# module.net
KiCad netlist of a schematic drawn in EAGLE
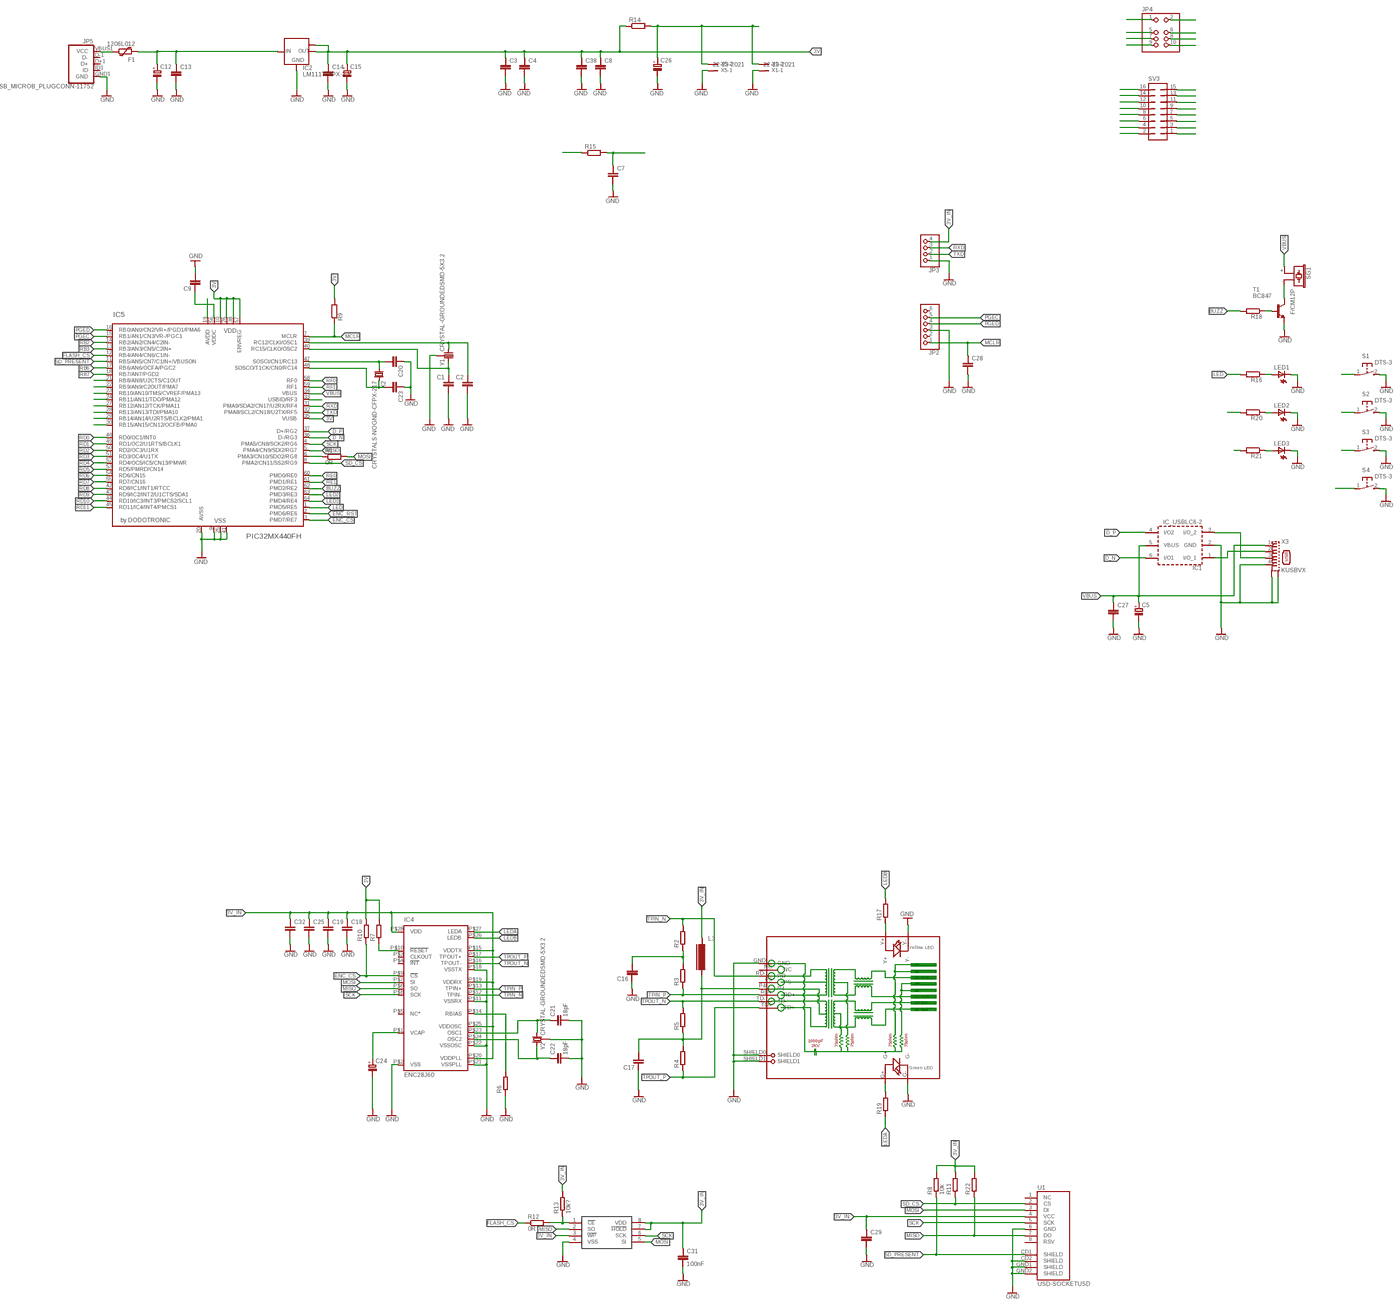
[diagram p0: schematic, sheet 1, overview]
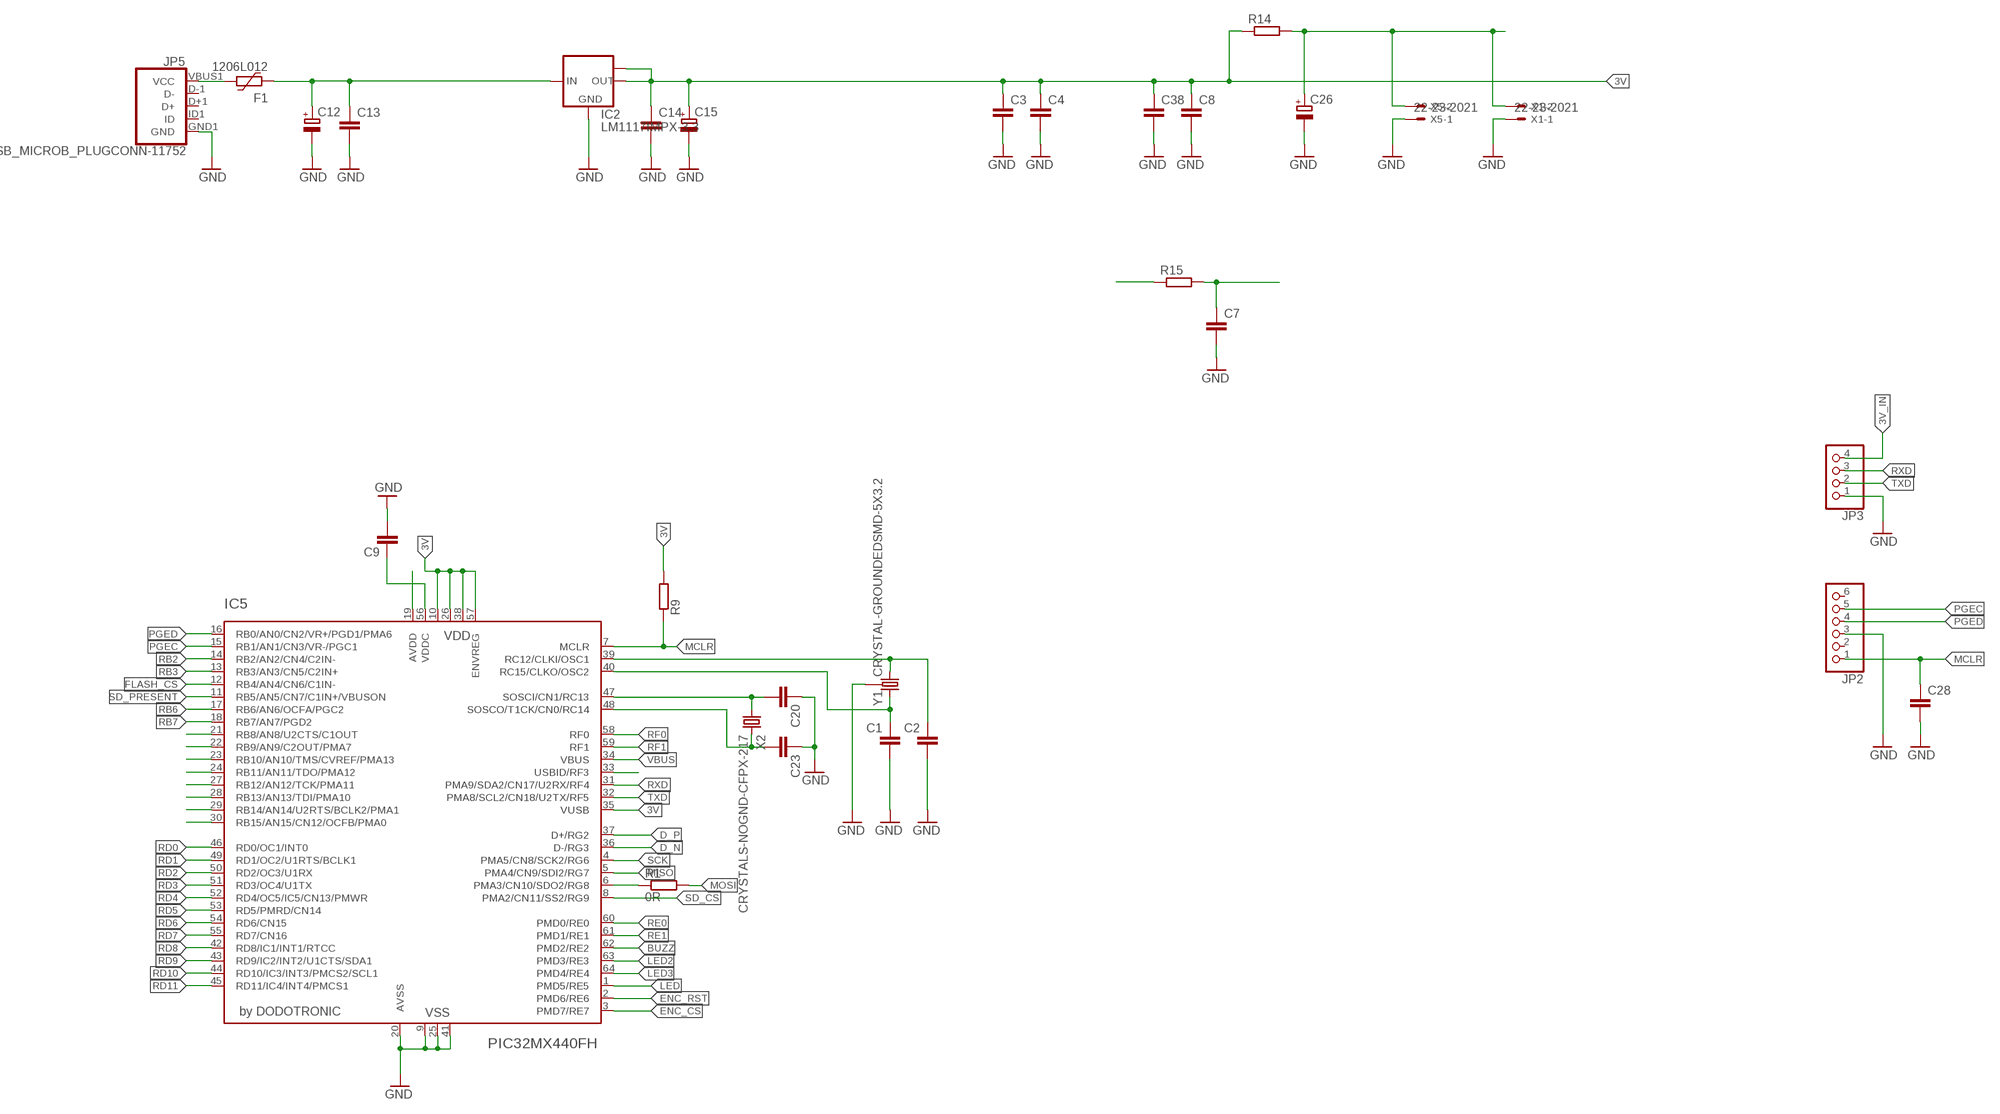
[diagram p1: schematic, sheet 1, part 1 of 4]
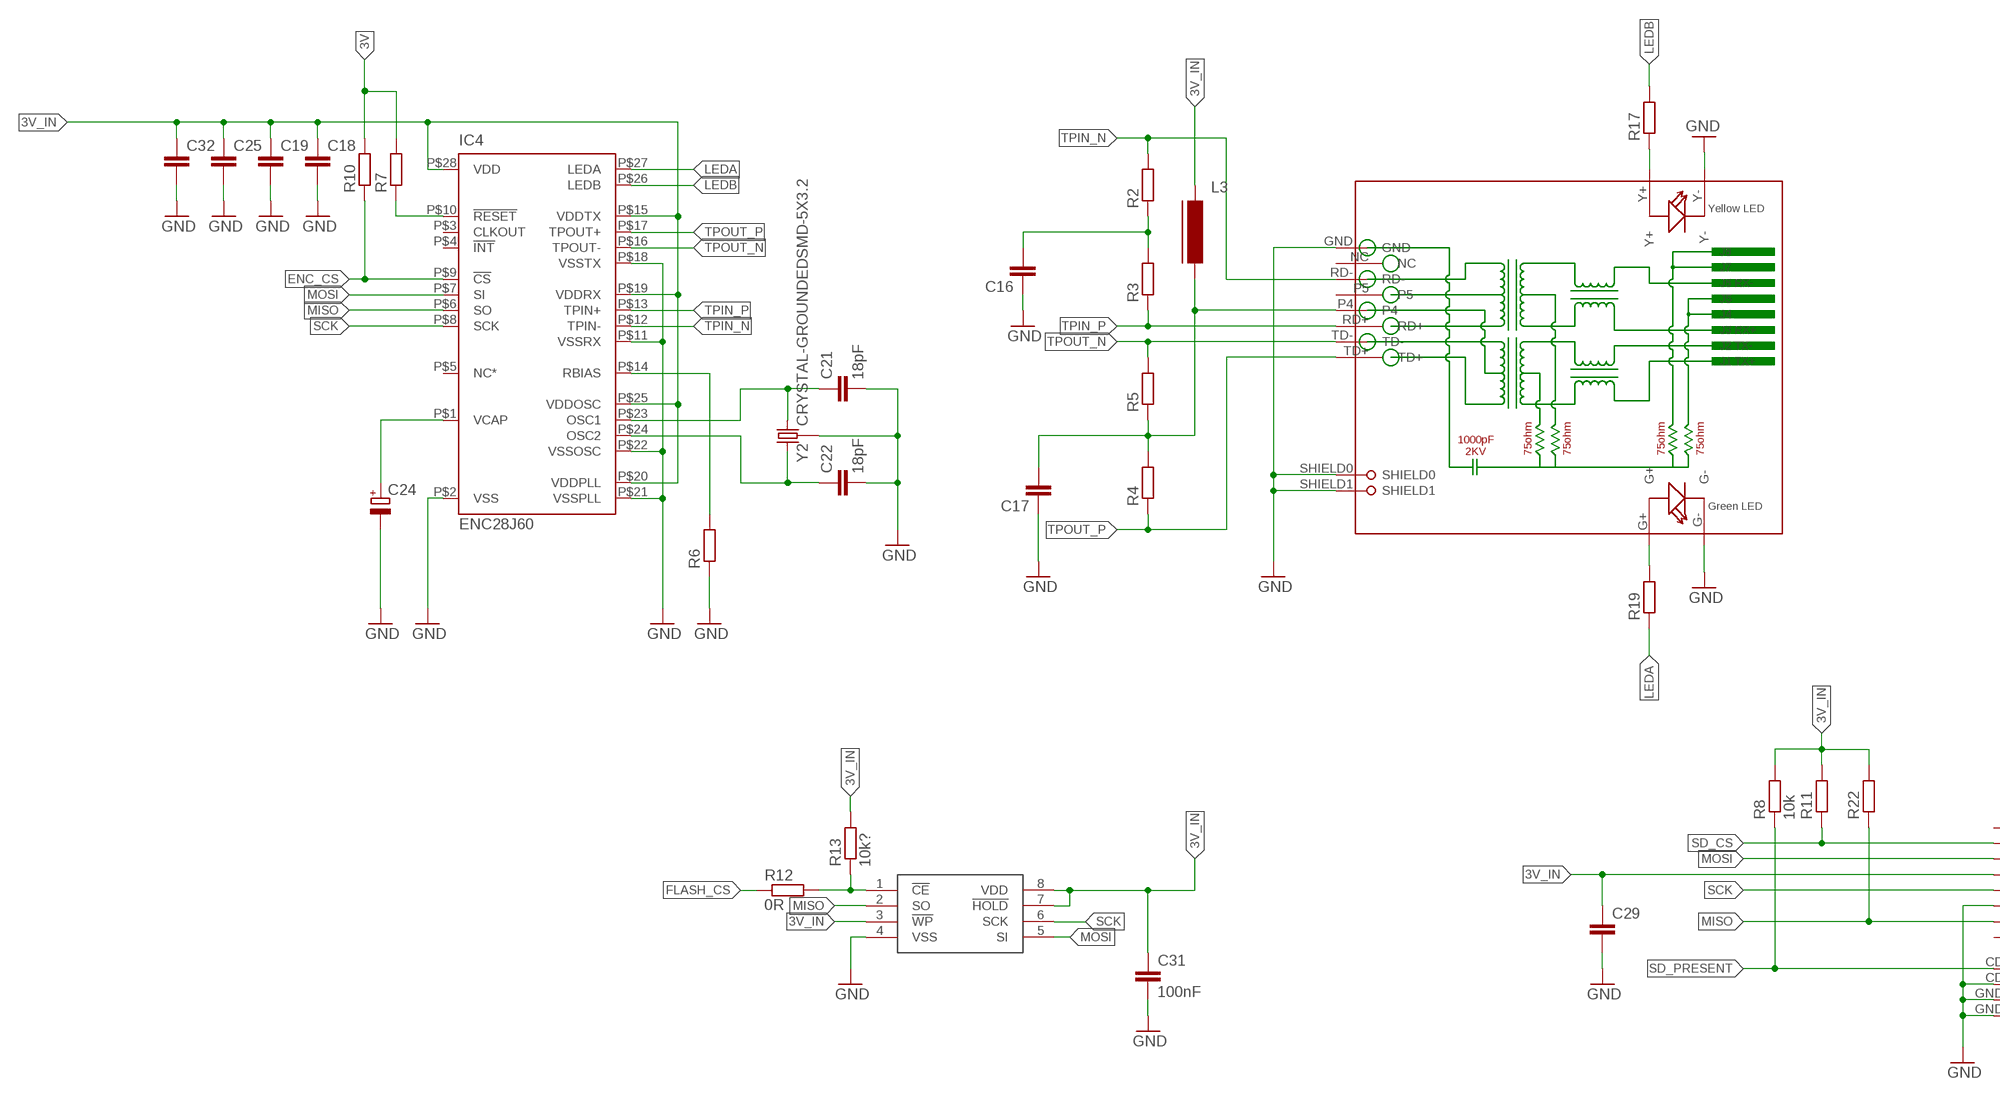
[diagram p2: schematic, sheet 1, part 2 of 4]
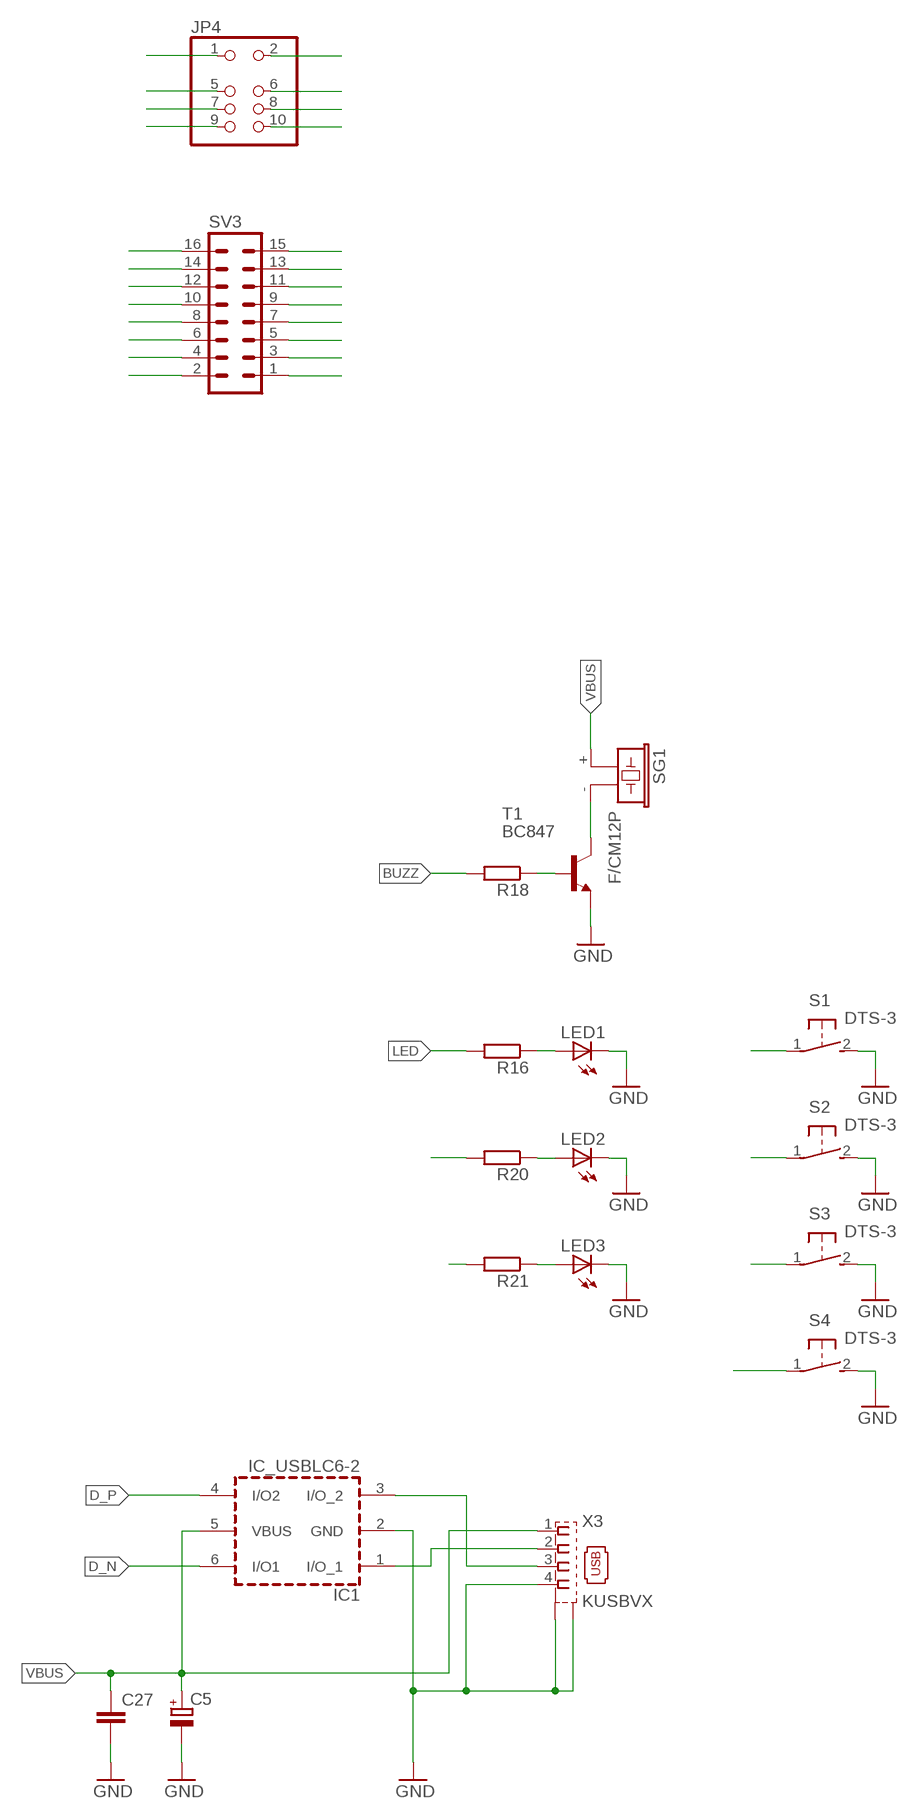
[diagram p3: schematic, sheet 1, part 3 of 4]
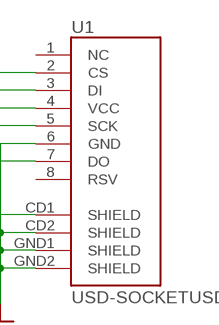
[diagram p4: schematic, sheet 1, part 4 of 4]

(export (version "E")
  (design (tool "Eeschema 10.0.6"))
  (components
    (comp (ref "C1")
      (value "C-EUC0603")
      (footprint "eagle-import:C0603")
      (libsource (lib "eagle-import") (part "C-EUC0603"))
    )
    (comp (ref "C2")
      (value "C-EUC0603")
      (footprint "eagle-import:C0603")
      (libsource (lib "eagle-import") (part "C-EUC0603"))
    )
    (comp (ref "C3")
      (value "C-EUC0402")
      (footprint "eagle-import:C0402")
      (libsource (lib "eagle-import") (part "C-EUC0402"))
    )
    (comp (ref "C4")
      (value "C-EUC0402")
      (footprint "eagle-import:C0402")
      (libsource (lib "eagle-import") (part "C-EUC0402"))
    )
    (comp (ref "C5")
      (value "CPOL-EUSMCA")
      (footprint "eagle-import:SMC_A")
      (libsource (lib "eagle-import") (part "CPOL-EUSMCA"))
    )
    (comp (ref "C7")
      (value "C-EUC0402")
      (footprint "eagle-import:C0402")
      (libsource (lib "eagle-import") (part "C-EUC0402"))
    )
    (comp (ref "C8")
      (value "C-EUC0402")
      (footprint "eagle-import:C0402")
      (libsource (lib "eagle-import") (part "C-EUC0402"))
    )
    (comp (ref "C9")
      (value "C-EUC0603")
      (footprint "eagle-import:C0603")
      (libsource (lib "eagle-import") (part "C-EUC0603"))
    )
    (comp (ref "C12")
      (value "CPOL-EUSMCB")
      (footprint "eagle-import:SMC_B")
      (libsource (lib "eagle-import") (part "CPOL-EUSMCB"))
    )
    (comp (ref "C13")
      (value "C-EUC0603")
      (footprint "eagle-import:C0603")
      (libsource (lib "eagle-import") (part "C-EUC0603"))
    )
    (comp (ref "C14")
      (value "C-EUC0603")
      (footprint "eagle-import:C0603")
      (libsource (lib "eagle-import") (part "C-EUC0603"))
    )
    (comp (ref "C15")
      (value "CPOL-EUSMCB")
      (footprint "eagle-import:SMC_B")
      (libsource (lib "eagle-import") (part "CPOL-EUSMCB"))
    )
    (comp (ref "C16")
      (value "C-EUC0603")
      (footprint "eagle-import:C0603")
      (libsource (lib "eagle-import") (part "C-EUC0603"))
    )
    (comp (ref "C17")
      (value "C-EUC0603")
      (footprint "eagle-import:C0603")
      (libsource (lib "eagle-import") (part "C-EUC0603"))
    )
    (comp (ref "C18")
      (value "C-EUC0402")
      (footprint "eagle-import:C0402")
      (libsource (lib "eagle-import") (part "C-EUC0402"))
    )
    (comp (ref "C19")
      (value "C-EUC0603")
      (footprint "eagle-import:C0603")
      (libsource (lib "eagle-import") (part "C-EUC0603"))
    )
    (comp (ref "C20")
      (value "C-EUC0603")
      (footprint "eagle-import:C0603")
      (libsource (lib "eagle-import") (part "C-EUC0603"))
    )
    (comp (ref "C21")
      (value "18pF")
      (footprint "eagle-import:C0603")
      (libsource (lib "eagle-import") (part "C-EUC0603"))
    )
    (comp (ref "C22")
      (value "18pF")
      (footprint "eagle-import:C0603")
      (libsource (lib "eagle-import") (part "C-EUC0603"))
    )
    (comp (ref "C23")
      (value "C-EUC0603")
      (footprint "eagle-import:C0603")
      (libsource (lib "eagle-import") (part "C-EUC0603"))
    )
    (comp (ref "C24")
      (value "CPOL-EUSMCA")
      (footprint "eagle-import:SMC_A")
      (libsource (lib "eagle-import") (part "CPOL-EUSMCA"))
    )
    (comp (ref "C25")
      (value "C-EUC0603")
      (footprint "eagle-import:C0603")
      (libsource (lib "eagle-import") (part "C-EUC0603"))
    )
    (comp (ref "C26")
      (value "CPOL-EUSMCA")
      (footprint "eagle-import:SMC_A")
      (libsource (lib "eagle-import") (part "CPOL-EUSMCA"))
    )
    (comp (ref "C27")
      (value "C-EUC0603")
      (footprint "eagle-import:C0603")
      (libsource (lib "eagle-import") (part "C-EUC0603"))
    )
    (comp (ref "C28")
      (value "C-EUC0603")
      (footprint "eagle-import:C0603")
      (libsource (lib "eagle-import") (part "C-EUC0603"))
    )
    (comp (ref "C29")
      (value "C-EUC0603")
      (footprint "eagle-import:C0603")
      (libsource (lib "eagle-import") (part "C-EUC0603"))
    )
    (comp (ref "C31")
      (value "100nF")
      (footprint "eagle-import:C0603")
      (libsource (lib "eagle-import") (part "C-EUC0603"))
    )
    (comp (ref "C32")
      (value "C-EUC0402")
      (footprint "eagle-import:C0402")
      (libsource (lib "eagle-import") (part "C-EUC0402"))
    )
    (comp (ref "C38")
      (value "C-EUC0603")
      (footprint "eagle-import:C0603")
      (libsource (lib "eagle-import") (part "C-EUC0603"))
    )
    (comp (ref "F1")
      (value "1206L012")
      (footprint "eagle-import:1206L")
      (fields (field (name "MF") "Littelfuse"))
      (libsource (lib "eagle-import") (part "?1206L012"))
    )
    (comp (ref "IC1")
      (value "IC_USBLC6-2")
      (footprint "eagle-import:SOT-23-6L")
      (libsource (lib "eagle-import") (part "IC_USBLC6-2"))
    )
    (comp (ref "IC2")
      (value "LM1117IMPX-3.3")
      (footprint "eagle-import:SOT223")
      (libsource (lib "eagle-import") (part "LM1117IMPX-3.3"))
    )
    (comp (ref "IC4")
      (value "ENC28J60")
      (footprint "eagle-import:TSSOP28W")
      (libsource (lib "eagle-import") (part "ENC28J60"))
    )
    (comp (ref "IC5")
      (value "PIC32MX440FH")
      (footprint "eagle-import:TQFP64-10X10")
      (libsource (lib "eagle-import") (part "PIC32MX440FH"))
    )
    (comp (ref "JP2")
      (value "PINHD-1X6")
      (footprint "eagle-import:1X06")
      (libsource (lib "eagle-import") (part "PINHD-1X6"))
    )
    (comp (ref "JP3")
      (value "PINHD-1X4")
      (footprint "eagle-import:1X04")
      (libsource (lib "eagle-import") (part "PINHD-1X4"))
    )
    (comp (ref "JP4")
      (value "PINHD-2X5")
      (footprint "eagle-import:2X05")
      (libsource (lib "eagle-import") (part "PINHD-2X5"))
    )
    (comp (ref "JP5")
      (value "USB_MICROB_PLUGCONN-11752")
      (footprint "eagle-import:USB-B-MICRO-SMD_V03")
      (libsource (lib "eagle-import") (part "USB_MICROB_PLUGCONN-11752"))
    )
    (comp (ref "L3")
      (value "FERRITE-0805")
      (footprint "eagle-import:FB805")
      (libsource (lib "eagle-import") (part "FERRITE-0805"))
    )
    (comp (ref "LED1")
      (value "LED3MM")
      (footprint "eagle-import:LED3MM")
      (libsource (lib "eagle-import") (part "LED3MM"))
    )
    (comp (ref "LED2")
      (value "LED3MM")
      (footprint "eagle-import:LED3MM")
      (libsource (lib "eagle-import") (part "LED3MM"))
    )
    (comp (ref "LED3")
      (value "LED3MM")
      (footprint "eagle-import:LED3MM")
      (libsource (lib "eagle-import") (part "LED3MM"))
    )
    (comp (ref "R1")
      (value "0R")
      (footprint "eagle-import:R0603")
      (libsource (lib "eagle-import") (part "R-EU_R0603"))
    )
    (comp (ref "R2")
      (value "R-EU_R0603")
      (footprint "eagle-import:R0603")
      (libsource (lib "eagle-import") (part "R-EU_R0603"))
    )
    (comp (ref "R3")
      (value "R-EU_R0603")
      (footprint "eagle-import:R0603")
      (libsource (lib "eagle-import") (part "R-EU_R0603"))
    )
    (comp (ref "R4")
      (value "R-EU_R0603")
      (footprint "eagle-import:R0603")
      (libsource (lib "eagle-import") (part "R-EU_R0603"))
    )
    (comp (ref "R5")
      (value "R-EU_R0603")
      (footprint "eagle-import:R0603")
      (libsource (lib "eagle-import") (part "R-EU_R0603"))
    )
    (comp (ref "R6")
      (value "R-EU_R0805")
      (footprint "eagle-import:R0805")
      (libsource (lib "eagle-import") (part "R-EU_R0805"))
    )
    (comp (ref "R7")
      (value "R-EU_R0402")
      (footprint "eagle-import:R0402")
      (libsource (lib "eagle-import") (part "R-EU_R0402"))
    )
    (comp (ref "R8")
      (value "10k")
      (footprint "eagle-import:R0603")
      (libsource (lib "eagle-import") (part "R-EU_R0603"))
    )
    (comp (ref "R9")
      (value "R-EU_R0603")
      (footprint "eagle-import:R0603")
      (libsource (lib "eagle-import") (part "R-EU_R0603"))
    )
    (comp (ref "R10")
      (value "R-EU_R0603")
      (footprint "eagle-import:R0603")
      (libsource (lib "eagle-import") (part "R-EU_R0603"))
    )
    (comp (ref "R11")
      (value "R-EU_R0603")
      (footprint "eagle-import:R0603")
      (libsource (lib "eagle-import") (part "R-EU_R0603"))
    )
    (comp (ref "R12")
      (value "0R")
      (footprint "eagle-import:R0603")
      (libsource (lib "eagle-import") (part "R-EU_R0603"))
    )
    (comp (ref "R13")
      (value "10k?")
      (footprint "eagle-import:R0603")
      (libsource (lib "eagle-import") (part "R-EU_R0603"))
    )
    (comp (ref "R14")
      (value "R-EU_R2010")
      (footprint "eagle-import:R2010")
      (libsource (lib "eagle-import") (part "R-EU_R2010"))
    )
    (comp (ref "R15")
      (value "R-EU_R0805")
      (footprint "eagle-import:R0805")
      (libsource (lib "eagle-import") (part "R-EU_R0805"))
    )
    (comp (ref "R16")
      (value "R-EU_R0603")
      (footprint "eagle-import:R0603")
      (libsource (lib "eagle-import") (part "R-EU_R0603"))
    )
    (comp (ref "R17")
      (value "R-EU_R1206")
      (footprint "eagle-import:R1206")
      (libsource (lib "eagle-import") (part "R-EU_R1206"))
    )
    (comp (ref "R18")
      (value "R-EU_R0603")
      (footprint "eagle-import:R0603")
      (libsource (lib "eagle-import") (part "R-EU_R0603"))
    )
    (comp (ref "R19")
      (value "R-EU_R1206")
      (footprint "eagle-import:R1206")
      (libsource (lib "eagle-import") (part "R-EU_R1206"))
    )
    (comp (ref "R20")
      (value "R-EU_R0603")
      (footprint "eagle-import:R0603")
      (libsource (lib "eagle-import") (part "R-EU_R0603"))
    )
    (comp (ref "R21")
      (value "R-EU_R0603")
      (footprint "eagle-import:R0603")
      (libsource (lib "eagle-import") (part "R-EU_R0603"))
    )
    (comp (ref "R22")
      (value "R-EU_R0603")
      (footprint "eagle-import:R0603")
      (libsource (lib "eagle-import") (part "R-EU_R0603"))
    )
    (comp (ref "RJ1")
      (value "HR911105A")
      (footprint "eagle-import:HR911105A")
      (libsource (lib "eagle-import") (part "HR911105A"))
    )
    (comp (ref "S1")
      (value "DTS-3")
      (footprint "eagle-import:DTS-3")
      (libsource (lib "eagle-import") (part "DTS-3"))
    )
    (comp (ref "S2")
      (value "DTS-3")
      (footprint "eagle-import:DTS-3")
      (libsource (lib "eagle-import") (part "DTS-3"))
    )
    (comp (ref "S3")
      (value "DTS-3")
      (footprint "eagle-import:DTS-3")
      (libsource (lib "eagle-import") (part "DTS-3"))
    )
    (comp (ref "S4")
      (value "DTS-3")
      (footprint "eagle-import:DTS-3")
      (libsource (lib "eagle-import") (part "DTS-3"))
    )
    (comp (ref "SG1")
      (value "F/CM12P")
      (footprint "eagle-import:F_CM12P")
      (libsource (lib "eagle-import") (part "F/CM12P"))
    )
    (comp (ref "SV3")
      (value "ML16L")
      (footprint "eagle-import:ML16L")
      (libsource (lib "eagle-import") (part "ML16L"))
    )
    (comp (ref "T1")
      (value "BC847")
      (footprint "eagle-import:SOT23")
      (libsource (lib "eagle-import") (part "BC847"))
    )
    (comp (ref "U$2")
      (value "SST25VF016BSO8M")
      (footprint "eagle-import:SO-08M")
      (libsource (lib "eagle-import") (part "SST25VF016BSO8M"))
    )
    (comp (ref "U1")
      (value "USD-SOCKETUSD")
      (footprint "eagle-import:USD-SOCKET-PP")
      (libsource (lib "eagle-import") (part "USD-SOCKETUSD"))
    )
    (comp (ref "X1")
      (value "22-23-2021")
      (footprint "eagle-import:22-23-2021")
      (fields (field (name "MF") "MOLEX"))
      (libsource (lib "eagle-import") (part "22-23-2021"))
    )
    (comp (ref "X2")
      (value "CRYSTALS-NOGND-CFPX-217")
      (footprint "eagle-import:3.2X1.5-2-PAD")
      (libsource (lib "eagle-import") (part "CRYSTALS-NOGND-CFPX-217"))
    )
    (comp (ref "X3")
      (value "KUSBVX")
      (footprint "eagle-import:KUSBVX")
      (libsource (lib "eagle-import") (part "KUSBVX"))
    )
    (comp (ref "X5")
      (value "22-23-2021")
      (footprint "eagle-import:22-23-2021")
      (fields (field (name "MF") "MOLEX"))
      (libsource (lib "eagle-import") (part "22-23-2021"))
    )
    (comp (ref "Y1")
      (value "CRYSTAL-GROUNDEDSMD-5X3.2")
      (footprint "eagle-import:CRYSTAL-SMD-5X3.2-4PAD")
      (libsource (lib "eagle-import") (part "CRYSTAL-GROUNDEDSMD-5X3.2"))
    )
    (comp (ref "Y2")
      (value "CRYSTAL-GROUNDEDSMD-5X3.2")
      (footprint "eagle-import:CRYSTAL-SMD-5X3.2-4PAD")
      (libsource (lib "eagle-import") (part "CRYSTAL-GROUNDEDSMD-5X3.2"))
    )
  )
  (nets
    (net (code "1") (name "/AV_3V") (class "Default")
      (node (ref "C7") (pin "1") (pinfunction "1_1") (pintype "passive"))
      (node (ref "IC5") (pin "19") (pinfunction "AVDD_19") (pintype "bidirectional"))
      (node (ref "R15") (pin "2") (pinfunction "2_2") (pintype "passive"))
    )
    (net (code "2") (name "/N$14") (class "Default")
      (node (ref "IC5") (pin "21") (pinfunction "RB8/AN8/U2CTS/C1OUT_21") (pintype "bidirectional"))
      (node (ref "JP4") (pin "9") (pinfunction "9_9") (pintype "passive"))
    )
    (net (code "3") (name "/N$15") (class "Default")
      (node (ref "IC5") (pin "22") (pinfunction "RB9/AN9/C2OUT/PMA7_22") (pintype "bidirectional"))
      (node (ref "JP4") (pin "10") (pinfunction "10_10") (pintype "passive"))
    )
    (net (code "4") (name "/N$16") (class "Default")
      (node (ref "IC5") (pin "23") (pinfunction "RB10/AN10/TMS/CVREF/PMA13_23") (pintype "bidirectional"))
      (node (ref "JP4") (pin "7") (pinfunction "7_7") (pintype "passive"))
    )
    (net (code "5") (name "/N$18") (class "Default")
      (node (ref "IC5") (pin "24") (pinfunction "RB11/AN11/TDO/PMA12_24") (pintype "bidirectional"))
      (node (ref "JP4") (pin "8") (pinfunction "8_8") (pintype "passive"))
    )
    (net (code "6") (name "/N$20") (class "Default")
      (node (ref "IC5") (pin "28") (pinfunction "RB13/AN13/TDI/PMA10_28") (pintype "bidirectional"))
      (node (ref "JP4") (pin "5") (pinfunction "5_5") (pintype "passive"))
    )
    (net (code "7") (name "/N$21") (class "Default")
      (node (ref "IC5") (pin "29") (pinfunction "RB14/AN14/U2RTS/BCLK2/PMA1_29") (pintype "bidirectional"))
      (node (ref "JP4") (pin "6") (pinfunction "6_6") (pintype "passive"))
    )
    (net (code "8") (name "/N$24") (class "Default")
      (node (ref "IC5") (pin "30") (pinfunction "RB15/AN15/CN12/OCFB/PMA0_30") (pintype "bidirectional"))
      (node (ref "JP4") (pin "1") (pinfunction "1_1") (pintype "passive"))
    )
    (net (code "9") (name "/N$25") (class "Default")
      (node (ref "IC5") (pin "33") (pinfunction "USBID/RF3_33") (pintype "bidirectional"))
      (node (ref "JP4") (pin "2") (pinfunction "2_2") (pintype "passive"))
    )
    (net (code "10") (name "3V") (class "Default")
      (node (ref "C14") (pin "1") (pinfunction "1_1") (pintype "passive"))
      (node (ref "C15") (pin "+") (pinfunction "+_+") (pintype "passive"))
      (node (ref "C3") (pin "1") (pinfunction "1_1") (pintype "passive"))
      (node (ref "C38") (pin "1") (pinfunction "1_1") (pintype "passive"))
      (node (ref "C4") (pin "1") (pinfunction "1_1") (pintype "passive"))
      (node (ref "C8") (pin "1") (pinfunction "1_1") (pintype "passive"))
      (node (ref "IC2") (pin "2") (pinfunction "OUT_2") (pintype "passive"))
      (node (ref "IC2") (pin "TAB") (pinfunction "OUT1_TAB") (pintype "passive"))
      (node (ref "IC5") (pin "10") (pinfunction "VDD_10") (pintype "power_in"))
      (node (ref "IC5") (pin "26") (pinfunction "VDD_26") (pintype "power_in"))
      (node (ref "IC5") (pin "35") (pinfunction "VUSB_35") (pintype "bidirectional"))
      (node (ref "IC5") (pin "38") (pinfunction "VDD_38") (pintype "power_in"))
      (node (ref "IC5") (pin "57") (pinfunction "ENVREG_57") (pintype "bidirectional"))
      (node (ref "R10") (pin "2") (pinfunction "2_2") (pintype "passive"))
      (node (ref "R14") (pin "1") (pinfunction "1_1") (pintype "passive"))
      (node (ref "R7") (pin "2") (pinfunction "2_2") (pintype "passive"))
      (node (ref "R9") (pin "2") (pinfunction "2_2") (pintype "passive"))
    )
    (net (code "11") (name "3V_IN") (class "Default")
      (node (ref "C18") (pin "1") (pinfunction "1_1") (pintype "passive"))
      (node (ref "C19") (pin "1") (pinfunction "1_1") (pintype "passive"))
      (node (ref "C25") (pin "1") (pinfunction "1_1") (pintype "passive"))
      (node (ref "C26") (pin "+") (pinfunction "+_+") (pintype "passive"))
      (node (ref "C29") (pin "1") (pinfunction "1_1") (pintype "passive"))
      (node (ref "C31") (pin "1") (pinfunction "1_1") (pintype "passive"))
      (node (ref "C32") (pin "1") (pinfunction "1_1") (pintype "passive"))
      (node (ref "IC4") (pin "P$15") (pinfunction "VDDTX_P$15") (pintype "input"))
      (node (ref "IC4") (pin "P$19") (pinfunction "VDDRX_P$19") (pintype "input"))
      (node (ref "IC4") (pin "P$20") (pinfunction "VDDPLL_P$20") (pintype "input"))
      (node (ref "IC4") (pin "P$25") (pinfunction "VDDOSC_P$25") (pintype "input"))
      (node (ref "IC4") (pin "P$28") (pinfunction "VDD_P$28") (pintype "input"))
      (node (ref "JP3") (pin "4") (pinfunction "4_4") (pintype "passive"))
      (node (ref "L3") (pin "1") (pinfunction "1_1") (pintype "passive"))
      (node (ref "R11") (pin "2") (pinfunction "2_2") (pintype "passive"))
      (node (ref "R13") (pin "2") (pinfunction "2_2") (pintype "passive"))
      (node (ref "R14") (pin "2") (pinfunction "2_2") (pintype "passive"))
      (node (ref "R15") (pin "1") (pinfunction "1_1") (pintype "passive"))
      (node (ref "R22") (pin "2") (pinfunction "2_2") (pintype "passive"))
      (node (ref "R8") (pin "2") (pinfunction "2_2") (pintype "passive"))
      (node (ref "U$2") (pin "3") (pinfunction "~{WP}_3") (pintype "bidirectional"))
      (node (ref "U$2") (pin "7") (pinfunction "~{HOLD}_7") (pintype "bidirectional"))
      (node (ref "U$2") (pin "8") (pinfunction "VDD_8") (pintype "bidirectional"))
      (node (ref "U1") (pin "4") (pinfunction "VCC_4") (pintype "bidirectional"))
      (node (ref "X1") (pin "2") (pinfunction "S_2") (pintype "passive"))
      (node (ref "X5") (pin "2") (pinfunction "S_2") (pintype "passive"))
    )
    (net (code "12") (name "BUZZ") (class "Default")
      (node (ref "IC5") (pin "62") (pinfunction "PMD2/RE2_62") (pintype "bidirectional"))
      (node (ref "R18") (pin "2") (pinfunction "2_2") (pintype "passive"))
    )
    (net (code "13") (name "D_N") (class "Default")
      (node (ref "IC1") (pin "6") (pinfunction "I/O1_6") (pintype "bidirectional"))
      (node (ref "IC5") (pin "36") (pinfunction "D-/RG3_36") (pintype "bidirectional"))
    )
    (net (code "14") (name "D_P") (class "Default")
      (node (ref "IC1") (pin "4") (pinfunction "I/O2_4") (pintype "bidirectional"))
      (node (ref "IC5") (pin "37") (pinfunction "D+/RG2_37") (pintype "bidirectional"))
    )
    (net (code "15") (name "ENC_CS") (class "Default")
      (node (ref "IC4") (pin "P$9") (pinfunction "~{CS}_P$9") (pintype "input"))
      (node (ref "IC5") (pin "3") (pinfunction "PMD7/RE7_3") (pintype "bidirectional"))
      (node (ref "R10") (pin "1") (pinfunction "1_1") (pintype "passive"))
    )
    (net (code "16") (name "ENC_RST") (class "Default")
      (node (ref "IC4") (pin "P$10") (pinfunction "~{RESET}_P$10") (pintype "input"))
      (node (ref "IC5") (pin "2") (pinfunction "PMD6/RE6_2") (pintype "bidirectional"))
      (node (ref "R7") (pin "1") (pinfunction "1_1") (pintype "passive"))
    )
    (net (code "17") (name "FLASH_CS") (class "Default")
      (node (ref "IC5") (pin "12") (pinfunction "RB4/AN4/CN6/C1IN-_12") (pintype "bidirectional"))
      (node (ref "R12") (pin "1") (pinfunction "1_1") (pintype "passive"))
    )
    (net (code "18") (name "GND") (class "Default")
      (node (ref "C1") (pin "2") (pinfunction "2_2") (pintype "passive"))
      (node (ref "C12") (pin "-") (pinfunction "-_-") (pintype "passive"))
      (node (ref "C13") (pin "2") (pinfunction "2_2") (pintype "passive"))
      (node (ref "C14") (pin "2") (pinfunction "2_2") (pintype "passive"))
      (node (ref "C15") (pin "-") (pinfunction "-_-") (pintype "passive"))
      (node (ref "C16") (pin "1") (pinfunction "1_1") (pintype "passive"))
      (node (ref "C17") (pin "1") (pinfunction "1_1") (pintype "passive"))
      (node (ref "C18") (pin "2") (pinfunction "2_2") (pintype "passive"))
      (node (ref "C19") (pin "2") (pinfunction "2_2") (pintype "passive"))
      (node (ref "C2") (pin "2") (pinfunction "2_2") (pintype "passive"))
      (node (ref "C20") (pin "1") (pinfunction "1_1") (pintype "passive"))
      (node (ref "C21") (pin "2") (pinfunction "2_2") (pintype "passive"))
      (node (ref "C22") (pin "2") (pinfunction "2_2") (pintype "passive"))
      (node (ref "C23") (pin "1") (pinfunction "1_1") (pintype "passive"))
      (node (ref "C24") (pin "-") (pinfunction "-_-") (pintype "passive"))
      (node (ref "C25") (pin "2") (pinfunction "2_2") (pintype "passive"))
      (node (ref "C26") (pin "-") (pinfunction "-_-") (pintype "passive"))
      (node (ref "C27") (pin "2") (pinfunction "2_2") (pintype "passive"))
      (node (ref "C28") (pin "2") (pinfunction "2_2") (pintype "passive"))
      (node (ref "C29") (pin "2") (pinfunction "2_2") (pintype "passive"))
      (node (ref "C3") (pin "2") (pinfunction "2_2") (pintype "passive"))
      (node (ref "C31") (pin "2") (pinfunction "2_2") (pintype "passive"))
      (node (ref "C32") (pin "2") (pinfunction "2_2") (pintype "passive"))
      (node (ref "C38") (pin "2") (pinfunction "2_2") (pintype "passive"))
      (node (ref "C4") (pin "2") (pinfunction "2_2") (pintype "passive"))
      (node (ref "C5") (pin "-") (pinfunction "-_-") (pintype "passive"))
      (node (ref "C7") (pin "2") (pinfunction "2_2") (pintype "passive"))
      (node (ref "C8") (pin "2") (pinfunction "2_2") (pintype "passive"))
      (node (ref "C9") (pin "2") (pinfunction "2_2") (pintype "passive"))
      (node (ref "IC1") (pin "2") (pinfunction "GND_2") (pintype "bidirectional"))
      (node (ref "IC2") (pin "1") (pinfunction "GND_1") (pintype "input"))
      (node (ref "IC4") (pin "P$11") (pinfunction "VSSRX_P$11") (pintype "input"))
      (node (ref "IC4") (pin "P$18") (pinfunction "VSSTX_P$18") (pintype "input"))
      (node (ref "IC4") (pin "P$2") (pinfunction "VSS_P$2") (pintype "input"))
      (node (ref "IC4") (pin "P$21") (pinfunction "VSSPLL_P$21") (pintype "input"))
      (node (ref "IC4") (pin "P$22") (pinfunction "VSSOSC_P$22") (pintype "input"))
      (node (ref "IC5") (pin "20") (pinfunction "AVSS_20") (pintype "bidirectional"))
      (node (ref "IC5") (pin "25") (pinfunction "VSS_25") (pintype "power_in"))
      (node (ref "IC5") (pin "41") (pinfunction "VSS_41") (pintype "power_in"))
      (node (ref "IC5") (pin "9") (pinfunction "VSS_9") (pintype "power_in"))
      (node (ref "JP2") (pin "3") (pinfunction "3_3") (pintype "passive"))
      (node (ref "JP3") (pin "1") (pinfunction "1_1") (pintype "passive"))
      (node (ref "JP5") (pin "GND1") (pinfunction "GND_GND1") (pintype "bidirectional"))
      (node (ref "LED1") (pin "K") (pinfunction "C_K") (pintype "passive"))
      (node (ref "LED2") (pin "K") (pinfunction "C_K") (pintype "passive"))
      (node (ref "LED3") (pin "K") (pinfunction "C_K") (pintype "passive"))
      (node (ref "R6") (pin "1") (pinfunction "1_1") (pintype "passive"))
      (node (ref "RJ1") (pin "G-") (pinfunction "G-_G-") (pintype "bidirectional"))
      (node (ref "RJ1") (pin "GND") (pinfunction "GND_GND") (pintype "bidirectional"))
      (node (ref "RJ1") (pin "SHIELD0") (pinfunction "SHIELD0_SHIELD0") (pintype "bidirectional"))
      (node (ref "RJ1") (pin "SHIELD1") (pinfunction "SHIELD1_SHIELD1") (pintype "bidirectional"))
      (node (ref "RJ1") (pin "Y-") (pinfunction "Y-_Y-") (pintype "bidirectional"))
      (node (ref "S1") (pin "2") (pinfunction "2_2") (pintype "passive"))
      (node (ref "S2") (pin "2") (pinfunction "2_2") (pintype "passive"))
      (node (ref "S3") (pin "2") (pinfunction "2_2") (pintype "passive"))
      (node (ref "S4") (pin "2") (pinfunction "2_2") (pintype "passive"))
      (node (ref "T1") (pin "2") (pinfunction "E_2") (pintype "passive"))
      (node (ref "U$2") (pin "4") (pinfunction "VSS_4") (pintype "bidirectional"))
      (node (ref "U1") (pin "6") (pinfunction "GND_6") (pintype "bidirectional"))
      (node (ref "U1") (pin "CD2") (pinfunction "SHIELD_CD2") (pintype "bidirectional"))
      (node (ref "U1") (pin "GND1") (pinfunction "SHIELD_GND1") (pintype "bidirectional"))
      (node (ref "U1") (pin "GND2") (pinfunction "SHIELD_GND2") (pintype "bidirectional"))
      (node (ref "X1") (pin "1") (pinfunction "S_1") (pintype "passive"))
      (node (ref "X3") (pin "4") (pinfunction "4_4") (pintype "passive"))
      (node (ref "X3") (pin "M1") (pinfunction "S1_M1") (pintype "passive"))
      (node (ref "X3") (pin "M2") (pinfunction "S2_M2") (pintype "passive"))
      (node (ref "X5") (pin "1") (pinfunction "S_1") (pintype "passive"))
      (node (ref "Y1") (pin "2") (pinfunction "3_2") (pintype "passive"))
      (node (ref "Y1") (pin "4") (pinfunction "3_4") (pintype "passive"))
      (node (ref "Y2") (pin "2") (pinfunction "3_2") (pintype "passive"))
      (node (ref "Y2") (pin "4") (pinfunction "3_4") (pintype "passive"))
    )
    (net (code "19") (name "LED") (class "Default")
      (node (ref "IC5") (pin "1") (pinfunction "PMD5/RE5_1") (pintype "bidirectional"))
      (node (ref "R16") (pin "2") (pinfunction "2_2") (pintype "passive"))
    )
    (net (code "20") (name "LED2") (class "Default")
      (node (ref "IC5") (pin "63") (pinfunction "PMD3/RE3_63") (pintype "bidirectional"))
      (node (ref "R20") (pin "2") (pinfunction "2_2") (pintype "passive"))
    )
    (net (code "21") (name "LED3") (class "Default")
      (node (ref "IC5") (pin "64") (pinfunction "PMD4/RE4_64") (pintype "bidirectional"))
      (node (ref "R21") (pin "2") (pinfunction "2_2") (pintype "passive"))
    )
    (net (code "22") (name "LEDA") (class "Default")
      (node (ref "IC4") (pin "P$27") (pinfunction "LEDA_P$27") (pintype "output"))
      (node (ref "R19") (pin "1") (pinfunction "1_1") (pintype "passive"))
    )
    (net (code "23") (name "LEDB") (class "Default")
      (node (ref "IC4") (pin "P$26") (pinfunction "LEDB_P$26") (pintype "output"))
      (node (ref "R17") (pin "2") (pinfunction "2_2") (pintype "passive"))
    )
    (net (code "24") (name "MCLR") (class "Default")
      (node (ref "C28") (pin "1") (pinfunction "1_1") (pintype "passive"))
      (node (ref "IC5") (pin "7") (pinfunction "MCLR_7") (pintype "bidirectional"))
      (node (ref "JP2") (pin "1") (pinfunction "1_1") (pintype "passive"))
      (node (ref "R9") (pin "1") (pinfunction "1_1") (pintype "passive"))
    )
    (net (code "25") (name "MISO") (class "Default")
      (node (ref "IC4") (pin "P$6") (pinfunction "SO_P$6") (pintype "output"))
      (node (ref "IC5") (pin "5") (pinfunction "PMA4/CN9/SDI2/RG7_5") (pintype "bidirectional"))
      (node (ref "R22") (pin "1") (pinfunction "1_1") (pintype "passive"))
      (node (ref "U$2") (pin "2") (pinfunction "SO_2") (pintype "bidirectional"))
      (node (ref "U1") (pin "7") (pinfunction "DO_7") (pintype "bidirectional"))
    )
    (net (code "26") (name "MOSI") (class "Default")
      (node (ref "IC4") (pin "P$7") (pinfunction "SI_P$7") (pintype "input"))
      (node (ref "R1") (pin "2") (pinfunction "2_2") (pintype "passive"))
      (node (ref "U$2") (pin "5") (pinfunction "SI_5") (pintype "bidirectional"))
      (node (ref "U1") (pin "3") (pinfunction "DI_3") (pintype "bidirectional"))
    )
    (net (code "27") (name "Net-(C16-Pad2)") (class "Default")
      (node (ref "C16") (pin "2") (pinfunction "2_2") (pintype "passive"))
      (node (ref "R2") (pin "1") (pinfunction "1_1") (pintype "passive"))
      (node (ref "R3") (pin "2") (pinfunction "2_2") (pintype "passive"))
    )
    (net (code "28") (name "Net-(C17-Pad2)") (class "Default")
      (node (ref "C17") (pin "2") (pinfunction "2_2") (pintype "passive"))
      (node (ref "L3") (pin "2") (pinfunction "2_2") (pintype "passive"))
      (node (ref "R4") (pin "2") (pinfunction "2_2") (pintype "passive"))
      (node (ref "R5") (pin "1") (pinfunction "1_1") (pintype "passive"))
      (node (ref "RJ1") (pin "P4") (pinfunction "P4_P4") (pintype "bidirectional"))
    )
    (net (code "29") (name "Net-(IC1-I{slash}O_1)") (class "Default")
      (node (ref "IC1") (pin "1") (pinfunction "I/O_1_1") (pintype "bidirectional"))
      (node (ref "X3") (pin "2") (pinfunction "2_2") (pintype "passive"))
    )
    (net (code "30") (name "Net-(IC1-I{slash}O_2)") (class "Default")
      (node (ref "IC1") (pin "3") (pinfunction "I/O_2_3") (pintype "bidirectional"))
      (node (ref "X3") (pin "3") (pinfunction "3_3") (pintype "passive"))
    )
    (net (code "31") (name "Net-(IC4-OSC1)") (class "Default")
      (node (ref "C21") (pin "1") (pinfunction "1_1") (pintype "passive"))
      (node (ref "IC4") (pin "P$23") (pinfunction "OSC1_P$23") (pintype "input"))
      (node (ref "Y2") (pin "1") (pinfunction "2_1") (pintype "passive"))
    )
    (net (code "32") (name "Net-(IC4-OSC2)") (class "Default")
      (node (ref "C22") (pin "1") (pinfunction "1_1") (pintype "passive"))
      (node (ref "IC4") (pin "P$24") (pinfunction "OSC2_P$24") (pintype "output"))
      (node (ref "Y2") (pin "3") (pinfunction "1_3") (pintype "passive"))
    )
    (net (code "33") (name "Net-(IC4-RBIAS)") (class "Default")
      (node (ref "IC4") (pin "P$14") (pinfunction "RBIAS_P$14") (pintype "input"))
      (node (ref "R6") (pin "2") (pinfunction "2_2") (pintype "passive"))
    )
    (net (code "34") (name "Net-(IC4-VCAP)") (class "Default")
      (node (ref "C24") (pin "+") (pinfunction "+_+") (pintype "passive"))
      (node (ref "IC4") (pin "P$1") (pinfunction "VCAP_P$1") (pintype "input"))
    )
    (net (code "35") (name "Net-(IC5-PMA3{slash}CN10{slash}SDO2{slash}RG8)") (class "Default")
      (node (ref "IC5") (pin "6") (pinfunction "PMA3/CN10/SDO2/RG8_6") (pintype "bidirectional"))
      (node (ref "R1") (pin "1") (pinfunction "1_1") (pintype "passive"))
    )
    (net (code "36") (name "Net-(IC5-RC12{slash}CLKI{slash}OSC1)") (class "Default")
      (node (ref "C2") (pin "1") (pinfunction "1_1") (pintype "passive"))
      (node (ref "IC5") (pin "39") (pinfunction "RC12/CLKI/OSC1_39") (pintype "bidirectional"))
      (node (ref "Y1") (pin "1") (pinfunction "2_1") (pintype "passive"))
    )
    (net (code "37") (name "Net-(IC5-RC15{slash}CLKO{slash}OSC2)") (class "Default")
      (node (ref "C1") (pin "1") (pinfunction "1_1") (pintype "passive"))
      (node (ref "IC5") (pin "40") (pinfunction "RC15/CLKO/OSC2_40") (pintype "bidirectional"))
      (node (ref "Y1") (pin "3") (pinfunction "1_3") (pintype "passive"))
    )
    (net (code "38") (name "Net-(IC5-SOSCI{slash}CN1{slash}RC13)") (class "Default")
      (node (ref "C20") (pin "2") (pinfunction "2_2") (pintype "passive"))
      (node (ref "IC5") (pin "47") (pinfunction "SOSCI/CN1/RC13_47") (pintype "bidirectional"))
      (node (ref "X2") (pin "1") (pinfunction "1_1") (pintype "passive"))
    )
    (net (code "39") (name "Net-(IC5-SOSCO{slash}T1CK{slash}CN0{slash}RC14)") (class "Default")
      (node (ref "C23") (pin "2") (pinfunction "2_2") (pintype "passive"))
      (node (ref "IC5") (pin "48") (pinfunction "SOSCO/T1CK/CN0/RC14_48") (pintype "bidirectional"))
      (node (ref "X2") (pin "2") (pinfunction "2_2") (pintype "passive"))
    )
    (net (code "40") (name "Net-(IC5-VDDC)") (class "Default")
      (node (ref "C9") (pin "1") (pinfunction "1_1") (pintype "passive"))
      (node (ref "IC5") (pin "56") (pinfunction "VDDC_56") (pintype "bidirectional"))
    )
    (net (code "41") (name "Net-(JP5-VCC)") (class "Default")
      (node (ref "F1") (pin "1") (pinfunction "1_1") (pintype "passive"))
      (node (ref "JP5") (pin "VBUS1") (pinfunction "VCC_VBUS1") (pintype "bidirectional"))
    )
    (net (code "42") (name "Net-(LED1-PadA)") (class "Default")
      (node (ref "LED1") (pin "A") (pinfunction "A_A") (pintype "passive"))
      (node (ref "R16") (pin "1") (pinfunction "1_1") (pintype "passive"))
    )
    (net (code "43") (name "Net-(LED2-PadA)") (class "Default")
      (node (ref "LED2") (pin "A") (pinfunction "A_A") (pintype "passive"))
      (node (ref "R20") (pin "1") (pinfunction "1_1") (pintype "passive"))
    )
    (net (code "44") (name "Net-(LED3-PadA)") (class "Default")
      (node (ref "LED3") (pin "A") (pinfunction "A_A") (pintype "passive"))
      (node (ref "R21") (pin "1") (pinfunction "1_1") (pintype "passive"))
    )
    (net (code "45") (name "Net-(R17-Pad1)") (class "Default")
      (node (ref "R17") (pin "1") (pinfunction "1_1") (pintype "passive"))
      (node (ref "RJ1") (pin "Y+") (pinfunction "Y+_Y+") (pintype "bidirectional"))
    )
    (net (code "46") (name "Net-(R19-Pad2)") (class "Default")
      (node (ref "R19") (pin "2") (pinfunction "2_2") (pintype "passive"))
      (node (ref "RJ1") (pin "G+") (pinfunction "G+_G+") (pintype "bidirectional"))
    )
    (net (code "47") (name "Net-(SG1-2)") (class "Default")
      (node (ref "SG1") (pin "-") (pinfunction "2_-") (pintype "passive"))
      (node (ref "T1") (pin "3") (pinfunction "C_3") (pintype "passive"))
    )
    (net (code "48") (name "Net-(T1-B)") (class "Default")
      (node (ref "R18") (pin "1") (pinfunction "1_1") (pintype "passive"))
      (node (ref "T1") (pin "1") (pinfunction "B_1") (pintype "passive"))
    )
    (net (code "49") (name "Net-(U$2-~{CE})") (class "Default")
      (node (ref "R12") (pin "2") (pinfunction "2_2") (pintype "passive"))
      (node (ref "R13") (pin "1") (pinfunction "1_1") (pintype "passive"))
      (node (ref "U$2") (pin "1") (pinfunction "~{CE}_1") (pintype "bidirectional"))
    )
    (net (code "50") (name "PGEC") (class "Default")
      (node (ref "IC5") (pin "15") (pinfunction "RB1/AN1/CN3/VR-/PGC1_15") (pintype "bidirectional"))
      (node (ref "JP2") (pin "5") (pinfunction "5_5") (pintype "passive"))
    )
    (net (code "51") (name "PGED") (class "Default")
      (node (ref "IC5") (pin "16") (pinfunction "RB0/AN0/CN2/VR+/PGD1/PMA6_16") (pintype "bidirectional"))
      (node (ref "JP2") (pin "4") (pinfunction "4_4") (pintype "passive"))
    )
    (net (code "52") (name "RB2") (class "Default")
      (node (ref "IC5") (pin "14") (pinfunction "RB2/AN2/CN4/C2IN-_14") (pintype "bidirectional"))
      (node (ref "S2") (pin "1") (pinfunction "1_1") (pintype "passive"))
    )
    (net (code "53") (name "RB3") (class "Default")
      (node (ref "IC5") (pin "13") (pinfunction "RB3/AN3/CN5/C2IN+_13") (pintype "bidirectional"))
      (node (ref "S1") (pin "1") (pinfunction "1_1") (pintype "passive"))
    )
    (net (code "54") (name "RB6") (class "Default")
      (node (ref "IC5") (pin "17") (pinfunction "RB6/AN6/OCFA/PGC2_17") (pintype "bidirectional"))
      (node (ref "S3") (pin "1") (pinfunction "1_1") (pintype "passive"))
    )
    (net (code "55") (name "RB7") (class "Default")
      (node (ref "IC5") (pin "18") (pinfunction "RB7/AN7/PGD2_18") (pintype "bidirectional"))
      (node (ref "S4") (pin "1") (pinfunction "1_1") (pintype "passive"))
    )
    (net (code "56") (name "RD0") (class "Default")
      (node (ref "IC5") (pin "46") (pinfunction "RD0/OC1/INT0_46") (pintype "bidirectional"))
      (node (ref "SV3") (pin "6") (pinfunction "6_6") (pintype "passive"))
    )
    (net (code "57") (name "RD1") (class "Default")
      (node (ref "IC5") (pin "49") (pinfunction "RD1/OC2/U1RTS/BCLK1_49") (pintype "bidirectional"))
      (node (ref "SV3") (pin "5") (pinfunction "5_5") (pintype "passive"))
    )
    (net (code "58") (name "RD2") (class "Default")
      (node (ref "IC5") (pin "50") (pinfunction "RD2/OC3/U1RX_50") (pintype "bidirectional"))
      (node (ref "SV3") (pin "8") (pinfunction "8_8") (pintype "passive"))
    )
    (net (code "59") (name "RD3") (class "Default")
      (node (ref "IC5") (pin "51") (pinfunction "RD3/OC4/U1TX_51") (pintype "bidirectional"))
      (node (ref "SV3") (pin "7") (pinfunction "7_7") (pintype "passive"))
    )
    (net (code "60") (name "RD4") (class "Default")
      (node (ref "IC5") (pin "52") (pinfunction "RD4/OC5/IC5/CN13/PMWR_52") (pintype "bidirectional"))
      (node (ref "SV3") (pin "10") (pinfunction "10_10") (pintype "passive"))
    )
    (net (code "61") (name "RD5") (class "Default")
      (node (ref "IC5") (pin "53") (pinfunction "RD5/PMRD/CN14_53") (pintype "bidirectional"))
      (node (ref "SV3") (pin "9") (pinfunction "9_9") (pintype "passive"))
    )
    (net (code "62") (name "RD6") (class "Default")
      (node (ref "IC5") (pin "54") (pinfunction "RD6/CN15_54") (pintype "bidirectional"))
      (node (ref "SV3") (pin "12") (pinfunction "12_12") (pintype "passive"))
    )
    (net (code "63") (name "RD7") (class "Default")
      (node (ref "IC5") (pin "55") (pinfunction "RD7/CN16_55") (pintype "bidirectional"))
      (node (ref "SV3") (pin "11") (pinfunction "11_11") (pintype "passive"))
    )
    (net (code "64") (name "RD8") (class "Default")
      (node (ref "IC5") (pin "42") (pinfunction "RD8/IC1/INT1/RTCC_42") (pintype "bidirectional"))
      (node (ref "SV3") (pin "2") (pinfunction "2_2") (pintype "passive"))
    )
    (net (code "65") (name "RD9") (class "Default")
      (node (ref "IC5") (pin "43") (pinfunction "RD9/IC2/INT2/U1CTS/SDA1_43") (pintype "bidirectional"))
      (node (ref "SV3") (pin "1") (pinfunction "1_1") (pintype "passive"))
    )
    (net (code "66") (name "RD10") (class "Default")
      (node (ref "IC5") (pin "44") (pinfunction "RD10/IC3/INT3/PMCS2/SCL1_44") (pintype "bidirectional"))
      (node (ref "SV3") (pin "4") (pinfunction "4_4") (pintype "passive"))
    )
    (net (code "67") (name "RD11") (class "Default")
      (node (ref "IC5") (pin "45") (pinfunction "RD11/IC4/INT4/PMCS1_45") (pintype "bidirectional"))
      (node (ref "SV3") (pin "3") (pinfunction "3_3") (pintype "passive"))
    )
    (net (code "68") (name "RE0") (class "Default")
      (node (ref "IC5") (pin "60") (pinfunction "PMD0/RE0_60") (pintype "bidirectional"))
      (node (ref "SV3") (pin "16") (pinfunction "16_16") (pintype "passive"))
    )
    (net (code "69") (name "RE1") (class "Default")
      (node (ref "IC5") (pin "61") (pinfunction "PMD1/RE1_61") (pintype "bidirectional"))
      (node (ref "SV3") (pin "15") (pinfunction "15_15") (pintype "passive"))
    )
    (net (code "70") (name "RF0") (class "Default")
      (node (ref "IC5") (pin "58") (pinfunction "RF0_58") (pintype "bidirectional"))
      (node (ref "SV3") (pin "14") (pinfunction "14_14") (pintype "passive"))
    )
    (net (code "71") (name "RF1") (class "Default")
      (node (ref "IC5") (pin "59") (pinfunction "RF1_59") (pintype "bidirectional"))
      (node (ref "SV3") (pin "13") (pinfunction "13_13") (pintype "passive"))
    )
    (net (code "72") (name "RXD") (class "Default")
      (node (ref "IC5") (pin "31") (pinfunction "PMA9/SDA2/CN17/U2RX/RF4_31") (pintype "bidirectional"))
      (node (ref "JP3") (pin "3") (pinfunction "3_3") (pintype "passive"))
    )
    (net (code "73") (name "SCK") (class "Default")
      (node (ref "IC4") (pin "P$8") (pinfunction "SCK_P$8") (pintype "input"))
      (node (ref "IC5") (pin "4") (pinfunction "PMA5/CN8/SCK2/RG6_4") (pintype "bidirectional"))
      (node (ref "U$2") (pin "6") (pinfunction "SCK_6") (pintype "bidirectional"))
      (node (ref "U1") (pin "5") (pinfunction "SCK_5") (pintype "bidirectional"))
    )
    (net (code "74") (name "SD_CS") (class "Default")
      (node (ref "IC5") (pin "8") (pinfunction "PMA2/CN11/SS2/RG9_8") (pintype "bidirectional"))
      (node (ref "R11") (pin "1") (pinfunction "1_1") (pintype "passive"))
      (node (ref "U1") (pin "2") (pinfunction "CS_2") (pintype "bidirectional"))
    )
    (net (code "75") (name "SD_PRESENT") (class "Default")
      (node (ref "IC5") (pin "11") (pinfunction "RB5/AN5/CN7/C1IN+/VBUSON_11") (pintype "bidirectional"))
      (node (ref "R8") (pin "1") (pinfunction "1_1") (pintype "passive"))
      (node (ref "U1") (pin "CD1") (pinfunction "SHIELD_CD1") (pintype "bidirectional"))
    )
    (net (code "76") (name "TPIN_N") (class "Default")
      (node (ref "IC4") (pin "P$12") (pinfunction "TPIN-_P$12") (pintype "input"))
      (node (ref "R2") (pin "2") (pinfunction "2_2") (pintype "passive"))
      (node (ref "RJ1") (pin "RD-") (pinfunction "RD-_RD-") (pintype "bidirectional"))
    )
    (net (code "77") (name "TPIN_P") (class "Default")
      (node (ref "IC4") (pin "P$13") (pinfunction "TPIN+_P$13") (pintype "input"))
      (node (ref "R3") (pin "1") (pinfunction "1_1") (pintype "passive"))
      (node (ref "RJ1") (pin "RD+") (pinfunction "RD+_RD+") (pintype "bidirectional"))
    )
    (net (code "78") (name "TPOUT_N") (class "Default")
      (node (ref "IC4") (pin "P$16") (pinfunction "TPOUT-_P$16") (pintype "output"))
      (node (ref "R5") (pin "2") (pinfunction "2_2") (pintype "passive"))
      (node (ref "RJ1") (pin "TD-") (pinfunction "TD-_TD-") (pintype "bidirectional"))
    )
    (net (code "79") (name "TPOUT_P") (class "Default")
      (node (ref "IC4") (pin "P$17") (pinfunction "TPOUT+_P$17") (pintype "output"))
      (node (ref "R4") (pin "1") (pinfunction "1_1") (pintype "passive"))
      (node (ref "RJ1") (pin "TD+") (pinfunction "TD+_TD+") (pintype "bidirectional"))
    )
    (net (code "80") (name "TXD") (class "Default")
      (node (ref "IC5") (pin "32") (pinfunction "PMA8/SCL2/CN18/U2TX/RF5_32") (pintype "bidirectional"))
      (node (ref "JP3") (pin "2") (pinfunction "2_2") (pintype "passive"))
    )
    (net (code "81") (name "VBUS") (class "Default")
      (node (ref "C12") (pin "+") (pinfunction "+_+") (pintype "passive"))
      (node (ref "C13") (pin "1") (pinfunction "1_1") (pintype "passive"))
      (node (ref "C27") (pin "1") (pinfunction "1_1") (pintype "passive"))
      (node (ref "C5") (pin "+") (pinfunction "+_+") (pintype "passive"))
      (node (ref "F1") (pin "2") (pinfunction "2_2") (pintype "passive"))
      (node (ref "IC1") (pin "5") (pinfunction "VBUS_5") (pintype "bidirectional"))
      (node (ref "IC2") (pin "3") (pinfunction "IN_3") (pintype "input"))
      (node (ref "IC5") (pin "34") (pinfunction "VBUS_34") (pintype "bidirectional"))
      (node (ref "SG1") (pin "+") (pinfunction "1_+") (pintype "passive"))
      (node (ref "X3") (pin "1") (pinfunction "1_1") (pintype "passive"))
    )
    (net (code "82") (name "unconnected-(IC4-CLKOUT-PadP$3)") (class "Default")
      (node (ref "IC4") (pin "P$3") (pinfunction "CLKOUT_P$3") (pintype "output"))
    )
    (net (code "83") (name "unconnected-(IC4-NC*-PadP$5)") (class "Default")
      (node (ref "IC4") (pin "P$5") (pinfunction "NC*_P$5") (pintype "output"))
    )
    (net (code "84") (name "unconnected-(IC4-~{INT}-PadP$4)") (class "Default")
      (node (ref "IC4") (pin "P$4") (pinfunction "~{INT}_P$4") (pintype "output"))
    )
    (net (code "85") (name "unconnected-(IC5-RB12{slash}AN12{slash}TCK{slash}PMA11-Pad27)") (class "Default")
      (node (ref "IC5") (pin "27") (pinfunction "RB12/AN12/TCK/PMA11_27") (pintype "bidirectional"))
    )
    (net (code "86") (name "unconnected-(JP2-Pad2)") (class "Default")
      (node (ref "JP2") (pin "2") (pinfunction "2_2") (pintype "passive"))
    )
    (net (code "87") (name "unconnected-(JP2-Pad6)") (class "Default")
      (node (ref "JP2") (pin "6") (pinfunction "6_6") (pintype "passive"))
    )
    (net (code "88") (name "unconnected-(JP5-D+-PadD+1)") (class "Default")
      (node (ref "JP5") (pin "D+1") (pinfunction "D+_D+1") (pintype "bidirectional"))
    )
    (net (code "89") (name "unconnected-(JP5-D--PadD-1)") (class "Default")
      (node (ref "JP5") (pin "D-1") (pinfunction "D-_D-1") (pintype "bidirectional"))
    )
    (net (code "90") (name "unconnected-(JP5-ID-PadID1)") (class "Default")
      (node (ref "JP5") (pin "ID1") (pinfunction "ID_ID1") (pintype "bidirectional"))
    )
    (net (code "91") (name "unconnected-(RJ1-PadNC)") (class "Default")
      (node (ref "RJ1") (pin "NC") (pinfunction "NC_NC") (pintype "bidirectional"))
    )
    (net (code "92") (name "unconnected-(RJ1-PadP5)") (class "Default")
      (node (ref "RJ1") (pin "P5") (pinfunction "P5_P5") (pintype "bidirectional"))
    )
    (net (code "93") (name "unconnected-(U1-NC-Pad1)") (class "Default")
      (node (ref "U1") (pin "1") (pinfunction "NC_1") (pintype "bidirectional"))
    )
    (net (code "94") (name "unconnected-(U1-RSV-Pad8)") (class "Default")
      (node (ref "U1") (pin "8") (pinfunction "RSV_8") (pintype "bidirectional"))
    )
  )
)
